# Power.net
KiCad netlist of a schematic drawn in Altium Designer
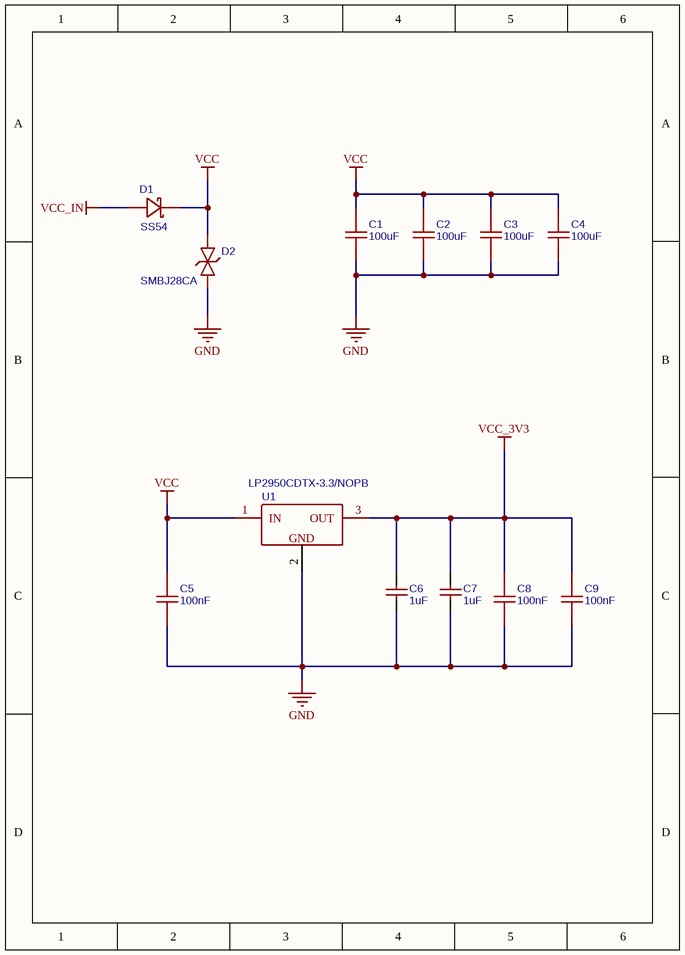
[diagram p0: Power.SchDoc]

(export (version "E")
  (design (tool "Eeschema 10.0.6"))
  (components
    (comp (ref "C1")
      (value "100uF")
      (footprint "C1206")
      (fields
        (field (name "BOM_SUPPLIER PART") "C312983")
        (field (name "BOM_MANUFACTURER PART") "GRM31CR61A107ME05L")
        (field (name "CONTRIBUTOR") "LCSC")
      )
      (libsource (lib "100uF") (part "100uF"))
    )
    (comp (ref "C2")
      (value "100uF")
      (footprint "C1206")
      (fields
        (field (name "BOM_SUPPLIER PART") "C312983")
        (field (name "BOM_MANUFACTURER PART") "GRM31CR61A107ME05L")
        (field (name "CONTRIBUTOR") "LCSC")
      )
      (libsource (lib "100uF") (part "100uF"))
    )
    (comp (ref "C3")
      (value "100uF")
      (footprint "C1206")
      (fields
        (field (name "BOM_SUPPLIER PART") "C312983")
        (field (name "BOM_MANUFACTURER PART") "GRM31CR61A107ME05L")
        (field (name "CONTRIBUTOR") "LCSC")
      )
      (libsource (lib "100uF") (part "100uF"))
    )
    (comp (ref "C4")
      (value "100uF")
      (footprint "C1206")
      (fields
        (field (name "BOM_SUPPLIER PART") "C312983")
        (field (name "BOM_MANUFACTURER PART") "GRM31CR61A107ME05L")
        (field (name "CONTRIBUTOR") "LCSC")
      )
      (libsource (lib "100uF") (part "100uF"))
    )
    (comp (ref "C5")
      (value "100nF")
      (footprint "C0603")
      (fields
        (field (name "BOM_MANUFACTURER PART") "CL10B104KB8NNNC")
        (field (name "BOM_SUPPLIER PART") "C1591")
      )
      (libsource (lib "0.1uF") (part "100nF"))
    )
    (comp (ref "C6")
      (value "1uF")
      (footprint "C0603")
      (fields
        (field (name "BOM_MANUFACTURER PART") "CL10A105KB8NNNC")
        (field (name "BOM_SUPPLIER PART") "C15849")
      )
      (libsource (lib "1uF") (part "1uF"))
    )
    (comp (ref "C7")
      (value "1uF")
      (footprint "C0603")
      (fields
        (field (name "BOM_MANUFACTURER PART") "CL10A105KB8NNNC")
        (field (name "BOM_SUPPLIER PART") "C15849")
      )
      (libsource (lib "1uF") (part "1uF"))
    )
    (comp (ref "C8")
      (value "100nF")
      (footprint "C0603")
      (fields
        (field (name "BOM_MANUFACTURER PART") "CL10B104KB8NNNC")
        (field (name "BOM_SUPPLIER PART") "C1591")
      )
      (libsource (lib "0.1uF") (part "100nF"))
    )
    (comp (ref "C9")
      (value "100nF")
      (footprint "C0603")
      (fields
        (field (name "BOM_MANUFACTURER PART") "CL10B104KB8NNNC")
        (field (name "BOM_SUPPLIER PART") "C1591")
      )
      (libsource (lib "0.1uF") (part "100nF"))
    )
    (comp (ref "D1")
      (value "SS54")
      (footprint "SMA_L4.3-W2.6-LS5.0-RD")
      (fields (field (name "BOM_SUPPLIER PART") "C727065") (field (name "CONTRIBUTOR") "LCSC"))
      (libsource (lib "SS54") (part "SS54_C727065"))
    )
    (comp (ref "D2")
      (value "SMBJ28CA")
      (footprint "SMB_L4.6-W3.6-LS5.3-BI")
      (fields (field (name "BOM_SUPPLIER PART") "C908204") (field (name "CONTRIBUTOR") "LCSC"))
      (libsource (lib "SMBJ28CA") (part "SMBJ28CA_C908204"))
    )
    (comp (ref "U1")
      (value "LP2950CDTX-3.3/NOPB")
      (footprint "TO-252-2_L6.6-W6.1-P4.57-LS9.9-BR-CW")
      (fields (field (name "BOM_SUPPLIER PART") "C129994") (field (name "CONTRIBUTOR") "LCSC"))
      (libsource (lib "30V 3.3V") (part "LP2950CDTX-3.3/NOPB"))
    )
  )
  (nets
    (net (code "1") (name "GND") (class "Default")
      (node (ref "C1") (pin "2") (pinfunction "2_2") (pintype "passive"))
      (node (ref "C2") (pin "2") (pinfunction "2_2") (pintype "passive"))
      (node (ref "C3") (pin "2") (pinfunction "2_2") (pintype "passive"))
      (node (ref "C4") (pin "2") (pinfunction "2_2") (pintype "passive"))
      (node (ref "C5") (pin "1") (pinfunction "1_1") (pintype "passive"))
      (node (ref "C6") (pin "1") (pinfunction "1_1") (pintype "passive"))
      (node (ref "C7") (pin "1") (pinfunction "1_1") (pintype "passive"))
      (node (ref "C8") (pin "1") (pinfunction "1_1") (pintype "passive"))
      (node (ref "C9") (pin "1") (pinfunction "1_1") (pintype "passive"))
      (node (ref "D2") (pin "1") (pinfunction "1_1") (pintype "passive"))
      (node (ref "U1") (pin "2") (pinfunction "GND_2") (pintype "passive"))
    )
    (net (code "2") (name "VCC") (class "Default")
      (node (ref "C1") (pin "1") (pinfunction "1_1") (pintype "passive"))
      (node (ref "C2") (pin "1") (pinfunction "1_1") (pintype "passive"))
      (node (ref "C3") (pin "1") (pinfunction "1_1") (pintype "passive"))
      (node (ref "C4") (pin "1") (pinfunction "1_1") (pintype "passive"))
      (node (ref "C5") (pin "2") (pinfunction "2_2") (pintype "passive"))
      (node (ref "D1") (pin "1") (pinfunction "1_1") (pintype "passive"))
      (node (ref "D2") (pin "2") (pinfunction "2_2") (pintype "passive"))
      (node (ref "U1") (pin "1") (pinfunction "IN_1") (pintype "passive"))
    )
    (net (code "3") (name "VCC_3V3") (class "Default")
      (node (ref "C6") (pin "2") (pinfunction "2_2") (pintype "passive"))
      (node (ref "C7") (pin "2") (pinfunction "2_2") (pintype "passive"))
      (node (ref "C8") (pin "2") (pinfunction "2_2") (pintype "passive"))
      (node (ref "C9") (pin "2") (pinfunction "2_2") (pintype "passive"))
      (node (ref "U1") (pin "3") (pinfunction "OUT_3") (pintype "passive"))
    )
    (net (code "4") (name "VCC_IN") (class "Default")
      (node (ref "D1") (pin "2") (pinfunction "2_2") (pintype "passive"))
    )
  )
)
